# schema5.net
KiCad netlist of a schematic drawn in Altium Designer
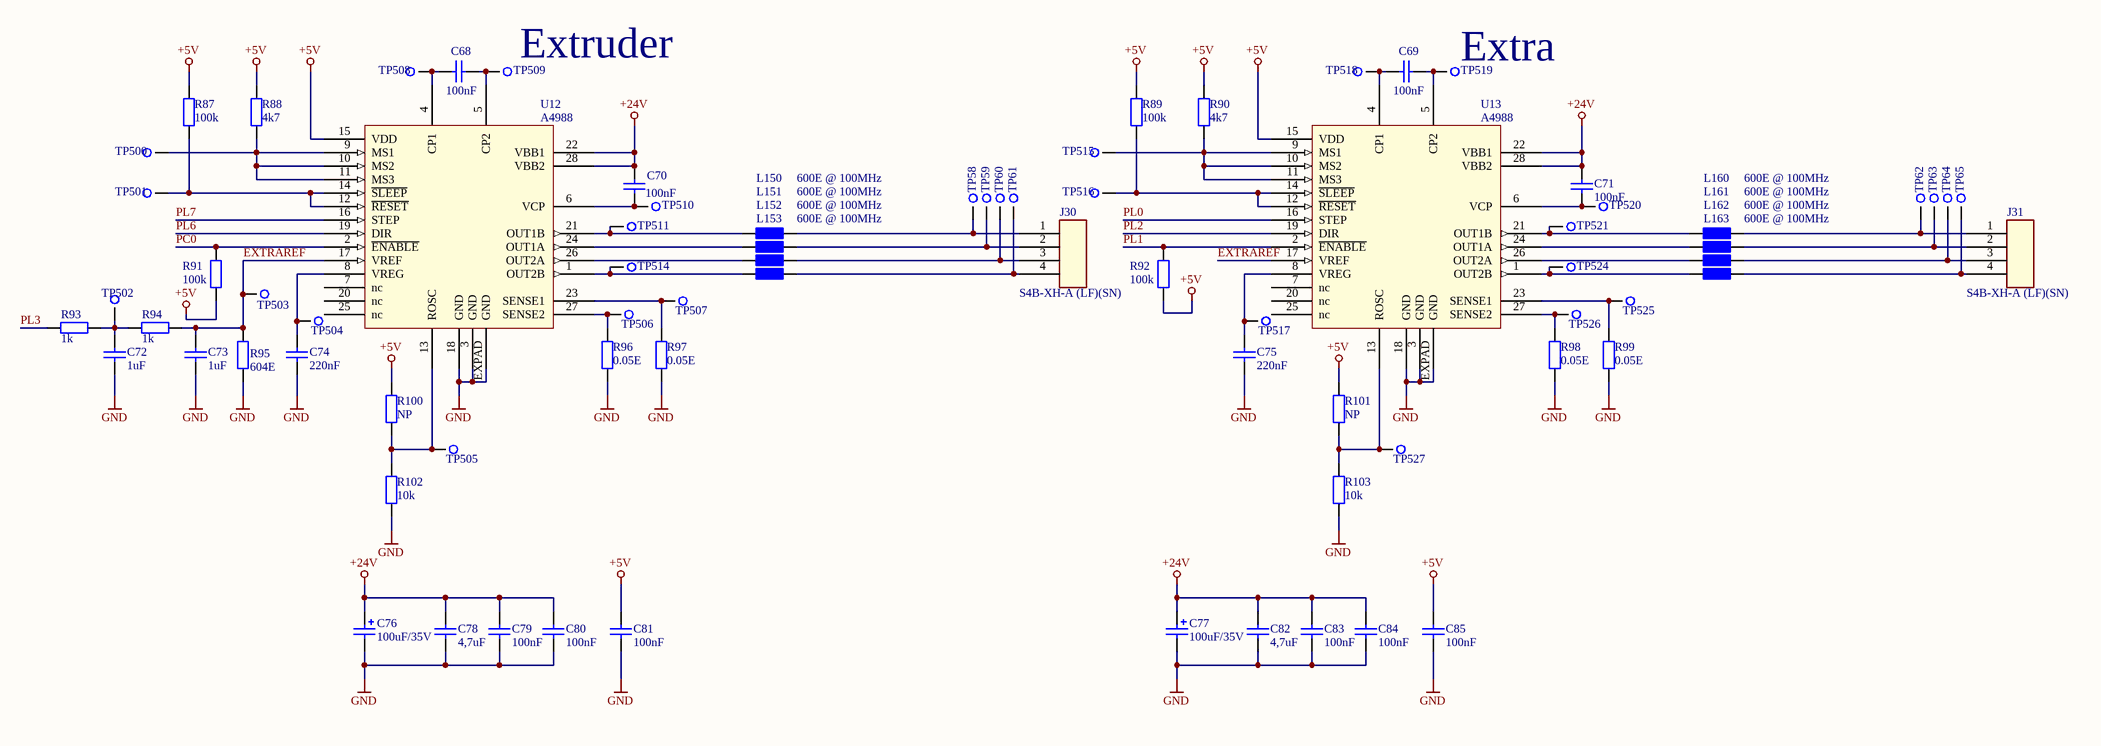
[diagram p0: schema5.SchDoc]

(export (version "E")
  (design (tool "Eeschema 10.0.6"))
  (components
    (comp (ref "C68")
      (value "100nF")
      (footprint "C0603")
      (description "RO X7R 100nF 10% 50V 0603")
      (libsource (lib "Database_Faber") (part "Capacitor"))
    )
    (comp (ref "C69")
      (value "100nF")
      (footprint "C0603")
      (description "RO X7R 100nF 10% 50V 0603")
      (libsource (lib "Database_Faber") (part "Capacitor"))
    )
    (comp (ref "C70")
      (value "100nF")
      (footprint "C0603")
      (description "RO X7R 100nF 10% 50V 0603")
      (libsource (lib "Database_Faber") (part "Capacitor"))
    )
    (comp (ref "C71")
      (value "100nF")
      (footprint "C0603")
      (description "RO X7R 100nF 10% 50V 0603")
      (libsource (lib "Database_Faber") (part "Capacitor"))
    )
    (comp (ref "C72")
      (value "1uF")
      (footprint "C0603")
      (description "RO X5R 1uF 10% 10V 0603")
      (libsource (lib "Database_Faber") (part "Capacitor"))
    )
    (comp (ref "C73")
      (value "1uF")
      (footprint "C0603")
      (description "RO X5R 1uF 10% 10V 0603")
      (libsource (lib "Database_Faber") (part "Capacitor"))
    )
    (comp (ref "C74")
      (value "220nF")
      (footprint "C0603")
      (description "RO X7R 220nF 10% 25V  0603")
      (libsource (lib "Database_Faber") (part "Capacitor"))
    )
    (comp (ref "C75")
      (value "220nF")
      (footprint "C0603")
      (description "RO X7R 220nF 10% 25V  0603")
      (libsource (lib "Database_Faber") (part "Capacitor"))
    )
    (comp (ref "C76")
      (value "100uF/35V")
      (footprint "ELCO Case D")
      (description "RO ELCO 100uF 20% 35V CASE-D EEEFP PAN")
      (libsource (lib "Database_Faber") (part "Capacitor Polarity"))
    )
    (comp (ref "C77")
      (value "100uF/35V")
      (footprint "ELCO Case D")
      (description "RO ELCO 100uF 20% 35V CASE-D EEEFP PAN")
      (libsource (lib "Database_Faber") (part "Capacitor Polarity"))
    )
    (comp (ref "C78")
      (value "4,7uF")
      (footprint "C1206")
      (description "RO X7R 4,7uF 10% 50V 1206")
      (libsource (lib "Database_Faber") (part "Capacitor"))
    )
    (comp (ref "C79")
      (value "100nF")
      (footprint "C0603")
      (description "RO X7R 100nF 10% 50V 0603")
      (libsource (lib "Database_Faber") (part "Capacitor"))
    )
    (comp (ref "C80")
      (value "100nF")
      (footprint "C0603")
      (description "RO X7R 100nF 10% 50V 0603")
      (libsource (lib "Database_Faber") (part "Capacitor"))
    )
    (comp (ref "C81")
      (value "100nF")
      (footprint "C0603")
      (description "RO X7R 100nF 10% 50V 0603")
      (libsource (lib "Database_Faber") (part "Capacitor"))
    )
    (comp (ref "C82")
      (value "4,7uF")
      (footprint "C1206")
      (description "RO X7R 4,7uF 10% 50V 1206")
      (libsource (lib "Database_Faber") (part "Capacitor"))
    )
    (comp (ref "C83")
      (value "100nF")
      (footprint "C0603")
      (description "RO X7R 100nF 10% 50V 0603")
      (libsource (lib "Database_Faber") (part "Capacitor"))
    )
    (comp (ref "C84")
      (value "100nF")
      (footprint "C0603")
      (description "RO X7R 100nF 10% 50V 0603")
      (libsource (lib "Database_Faber") (part "Capacitor"))
    )
    (comp (ref "C85")
      (value "100nF")
      (footprint "C0603")
      (description "RO X7R 100nF 10% 50V 0603")
      (libsource (lib "Database_Faber") (part "Capacitor"))
    )
    (comp (ref "J30")
      (value "S4B-XH-A (LF)(SN)")
      (footprint "S4B-XH-A (LF)(SN)")
      (description "RO CONN PR 4p HKS S4B-XH-A (LF)(SN) JST")
      (fields (field (name "MFG") "JST (JAPAN SOLDERLESS TERMINALS)"))
      (libsource (lib "Database_Faber") (part "HEADER 4"))
    )
    (comp (ref "J31")
      (value "S4B-XH-A (LF)(SN)")
      (footprint "S4B-XH-A (LF)(SN)")
      (description "RO CONN PR 4p HKS S4B-XH-A (LF)(SN) JST")
      (fields (field (name "MFG") "JST (JAPAN SOLDERLESS TERMINALS)"))
      (libsource (lib "Database_Faber") (part "HEADER 4"))
    )
    (comp (ref "L150")
      (value "600E @ 100MHz")
      (footprint "R1206")
      (description "FERRIET 742792118 1206 Wurth Elektronik")
      (fields (field (name "MFG") "Wurth Elektronics"))
      (libsource (lib "Ultimaker") (part "Ferriet Bead 600E"))
    )
    (comp (ref "L151")
      (value "600E @ 100MHz")
      (footprint "R1206")
      (description "FERRIET 742792118 1206 Wurth Elektronik")
      (fields (field (name "MFG") "Wurth Elektronics"))
      (libsource (lib "Ultimaker") (part "Ferriet Bead 600E"))
    )
    (comp (ref "L152")
      (value "600E @ 100MHz")
      (footprint "R1206")
      (description "FERRIET 742792118 1206 Wurth Elektronik")
      (fields (field (name "MFG") "Wurth Elektronics"))
      (libsource (lib "Ultimaker") (part "Ferriet Bead 600E"))
    )
    (comp (ref "L153")
      (value "600E @ 100MHz")
      (footprint "R1206")
      (description "FERRIET 742792118 1206 Wurth Elektronik")
      (fields (field (name "MFG") "Wurth Elektronics"))
      (libsource (lib "Ultimaker") (part "Ferriet Bead 600E"))
    )
    (comp (ref "L160")
      (value "600E @ 100MHz")
      (footprint "R1206")
      (description "FERRIET 742792118 1206 Wurth Elektronik")
      (fields (field (name "MFG") "Wurth Elektronics"))
      (libsource (lib "Ultimaker") (part "Ferriet Bead 600E"))
    )
    (comp (ref "L161")
      (value "600E @ 100MHz")
      (footprint "R1206")
      (description "FERRIET 742792118 1206 Wurth Elektronik")
      (fields (field (name "MFG") "Wurth Elektronics"))
      (libsource (lib "Ultimaker") (part "Ferriet Bead 600E"))
    )
    (comp (ref "L162")
      (value "600E @ 100MHz")
      (footprint "R1206")
      (description "FERRIET 742792118 1206 Wurth Elektronik")
      (fields (field (name "MFG") "Wurth Elektronics"))
      (libsource (lib "Ultimaker") (part "Ferriet Bead 600E"))
    )
    (comp (ref "L163")
      (value "600E @ 100MHz")
      (footprint "R1206")
      (description "FERRIET 742792118 1206 Wurth Elektronik")
      (fields (field (name "MFG") "Wurth Elektronics"))
      (libsource (lib "Ultimaker") (part "Ferriet Bead 600E"))
    )
    (comp (ref "R87")
      (value "100k")
      (footprint "R0603")
      (description "RO RES 100k0 1% 0,063W  0603")
      (libsource (lib "Database_Faber") (part "Resistor"))
    )
    (comp (ref "R88")
      (value "4k7")
      (footprint "R0603")
      (description "RO RES 4k70 1% 0,063W  0603")
      (libsource (lib "Database_Faber") (part "Resistor"))
    )
    (comp (ref "R89")
      (value "100k")
      (footprint "R0603")
      (description "RO RES 100k0 1% 0,063W  0603")
      (libsource (lib "Database_Faber") (part "Resistor"))
    )
    (comp (ref "R90")
      (value "4k7")
      (footprint "R0603")
      (description "RO RES 4k70 1% 0,063W  0603")
      (libsource (lib "Database_Faber") (part "Resistor"))
    )
    (comp (ref "R91")
      (value "100k")
      (footprint "R0603")
      (description "RO RES 100k0 1% 0,063W  0603")
      (libsource (lib "") (part "Resistor_2"))
    )
    (comp (ref "R92")
      (value "100k")
      (footprint "R0603")
      (description "RO RES 100k0 1% 0,063W  0603")
      (libsource (lib "") (part "Resistor_2"))
    )
    (comp (ref "R93")
      (value "1k")
      (footprint "R0603")
      (description "RO RES 1k0 1% 0,1W  0603")
      (libsource (lib "") (part "Resistor_1"))
    )
    (comp (ref "R94")
      (value "1k")
      (footprint "R0603")
      (description "RO RES 1k0 1% 0,1W  0603")
      (libsource (lib "") (part "Resistor_1"))
    )
    (comp (ref "R95")
      (value "604E")
      (footprint "R0603")
      (description "RO RES 604E 1% 0,063W 0603")
      (fields (field (name "MFG") "VISHAY DRALORIC"))
      (libsource (lib "Database_Faber") (part "Resistor"))
    )
    (comp (ref "R96")
      (value "0.05E")
      (footprint "R0805")
      (description "RO RES 0E05 1% 0,125W 0805")
      (fields (field (name "MFG") "BOURNS"))
      (libsource (lib "Database_Faber") (part "Resistor"))
    )
    (comp (ref "R97")
      (value "0.05E")
      (footprint "R0805")
      (description "RO RES 0E05 1% 0,125W 0805")
      (fields (field (name "MFG") "BOURNS"))
      (libsource (lib "Database_Faber") (part "Resistor"))
    )
    (comp (ref "R98")
      (value "0.05E")
      (footprint "R0805")
      (description "RO RES 0E05 1% 0,125W 0805")
      (fields (field (name "MFG") "BOURNS"))
      (libsource (lib "Database_Faber") (part "Resistor"))
    )
    (comp (ref "R99")
      (value "0.05E")
      (footprint "R0805")
      (description "RO RES 0E05 1% 0,125W 0805")
      (fields (field (name "MFG") "BOURNS"))
      (libsource (lib "Database_Faber") (part "Resistor"))
    )
    (comp (ref "R100") (value "NP") (footprint "R0603") (libsource (lib "Database_Faber") (part "Resistor")))
    (comp (ref "R101") (value "NP") (footprint "R0603") (libsource (lib "Database_Faber") (part "Resistor")))
    (comp (ref "R102")
      (value "10k")
      (footprint "R0603")
      (description "RO RES 10k0 1% 0,063W  0603")
      (libsource (lib "Database_Faber") (part "Resistor"))
    )
    (comp (ref "R103")
      (value "10k")
      (footprint "R0603")
      (description "RO RES 10k0 1% 0,063W  0603")
      (libsource (lib "Database_Faber") (part "Resistor"))
    )
    (comp (ref "TP58")
      (value "Testpoint")
      (footprint "Testpoint")
      (libsource (lib "Database_Faber") (part "Testpoint"))
    )
    (comp (ref "TP59")
      (value "Testpoint")
      (footprint "Testpoint")
      (libsource (lib "Database_Faber") (part "Testpoint"))
    )
    (comp (ref "TP60")
      (value "Testpoint")
      (footprint "Testpoint")
      (libsource (lib "Database_Faber") (part "Testpoint"))
    )
    (comp (ref "TP61")
      (value "Testpoint")
      (footprint "Testpoint")
      (libsource (lib "Database_Faber") (part "Testpoint"))
    )
    (comp (ref "TP62")
      (value "Testpoint")
      (footprint "Testpoint")
      (libsource (lib "Database_Faber") (part "Testpoint"))
    )
    (comp (ref "TP63")
      (value "Testpoint")
      (footprint "Testpoint")
      (libsource (lib "Database_Faber") (part "Testpoint"))
    )
    (comp (ref "TP64")
      (value "Testpoint")
      (footprint "Testpoint")
      (libsource (lib "Database_Faber") (part "Testpoint"))
    )
    (comp (ref "TP65")
      (value "Testpoint")
      (footprint "Testpoint")
      (libsource (lib "Database_Faber") (part "Testpoint"))
    )
    (comp (ref "TP500")
      (value "Testpoint")
      (footprint "TESTPOINT")
      (libsource (lib "Ultimaker") (part "Testpoint 1mm"))
    )
    (comp (ref "TP501")
      (value "Testpoint")
      (footprint "TESTPOINT")
      (libsource (lib "Ultimaker") (part "Testpoint 1mm"))
    )
    (comp (ref "TP502")
      (value "Testpoint 1mm")
      (footprint "Testpoint 1mm")
      (libsource (lib "Ultimaker") (part "Testpoint 1mm"))
    )
    (comp (ref "TP503")
      (value "Testpoint 1mm")
      (footprint "Testpoint 1mm")
      (libsource (lib "Ultimaker") (part "Testpoint 1mm"))
    )
    (comp (ref "TP504")
      (value "Testpoint 1mm")
      (footprint "Testpoint 1mm")
      (libsource (lib "Ultimaker") (part "Testpoint 1mm"))
    )
    (comp (ref "TP505")
      (value "Testpoint 1mm")
      (footprint "Testpoint 1mm")
      (libsource (lib "Ultimaker") (part "Testpoint 1mm"))
    )
    (comp (ref "TP506")
      (value "Testpoint 1mm")
      (footprint "Testpoint 1mm")
      (libsource (lib "Ultimaker") (part "Testpoint 1mm"))
    )
    (comp (ref "TP507")
      (value "Testpoint 1mm")
      (footprint "Testpoint 1mm")
      (libsource (lib "Ultimaker") (part "Testpoint 1mm"))
    )
    (comp (ref "TP508")
      (value "Testpoint 1mm")
      (footprint "Testpoint 1mm")
      (libsource (lib "Ultimaker") (part "Testpoint 1mm"))
    )
    (comp (ref "TP509")
      (value "Testpoint 1mm")
      (footprint "Testpoint 1mm")
      (libsource (lib "Ultimaker") (part "Testpoint 1mm"))
    )
    (comp (ref "TP510")
      (value "Testpoint 1mm")
      (footprint "Testpoint 1mm")
      (libsource (lib "Ultimaker") (part "Testpoint 1mm"))
    )
    (comp (ref "TP511")
      (value "Testpoint 1mm")
      (footprint "Testpoint 1mm")
      (libsource (lib "Ultimaker") (part "Testpoint 1mm"))
    )
    (comp (ref "TP514")
      (value "Testpoint 1mm")
      (footprint "Testpoint 1mm")
      (libsource (lib "Ultimaker") (part "Testpoint 1mm"))
    )
    (comp (ref "TP515")
      (value "Testpoint")
      (footprint "TESTPOINT")
      (libsource (lib "Ultimaker") (part "Testpoint 1mm"))
    )
    (comp (ref "TP516")
      (value "Testpoint")
      (footprint "TESTPOINT")
      (libsource (lib "Ultimaker") (part "Testpoint 1mm"))
    )
    (comp (ref "TP517")
      (value "Testpoint 1mm")
      (footprint "Testpoint 1mm")
      (libsource (lib "Ultimaker") (part "Testpoint 1mm"))
    )
    (comp (ref "TP518")
      (value "Testpoint 1mm")
      (footprint "Testpoint 1mm")
      (libsource (lib "Ultimaker") (part "Testpoint 1mm"))
    )
    (comp (ref "TP519")
      (value "Testpoint 1mm")
      (footprint "Testpoint 1mm")
      (libsource (lib "Ultimaker") (part "Testpoint 1mm"))
    )
    (comp (ref "TP520")
      (value "Testpoint 1mm")
      (footprint "Testpoint 1mm")
      (libsource (lib "Ultimaker") (part "Testpoint 1mm"))
    )
    (comp (ref "TP521")
      (value "Testpoint 1mm")
      (footprint "Testpoint 1mm")
      (libsource (lib "Ultimaker") (part "Testpoint 1mm"))
    )
    (comp (ref "TP524")
      (value "Testpoint 1mm")
      (footprint "Testpoint 1mm")
      (libsource (lib "Ultimaker") (part "Testpoint 1mm"))
    )
    (comp (ref "TP525")
      (value "Testpoint 1mm")
      (footprint "Testpoint 1mm")
      (libsource (lib "Ultimaker") (part "Testpoint 1mm"))
    )
    (comp (ref "TP526")
      (value "Testpoint 1mm")
      (footprint "Testpoint 1mm")
      (libsource (lib "Ultimaker") (part "Testpoint 1mm"))
    )
    (comp (ref "TP527")
      (value "Testpoint 1mm")
      (footprint "Testpoint 1mm")
      (libsource (lib "Ultimaker") (part "Testpoint 1mm"))
    )
    (comp (ref "U12")
      (value "A4988")
      (footprint "QFN50P500X500X100-28-EX")
      (description "RO IC A4988 QFN-28 ALLEGRO")
      (fields (field (name "MFG") "Allegro"))
      (libsource (lib "Database_Faber") (part "A4988"))
    )
    (comp (ref "U13")
      (value "A4988")
      (footprint "QFN50P500X500X100-28-EX")
      (description "RO IC A4988 QFN-28 ALLEGRO")
      (fields (field (name "MFG") "Allegro"))
      (libsource (lib "Database_Faber") (part "A4988"))
    )
  )
  (nets
    (net (code "1") (name "+5V") (class "Default")
      (node (ref "C81") (pin "2") (pinfunction "2_2") (pintype "passive"))
      (node (ref "C85") (pin "2") (pinfunction "2_2") (pintype "passive"))
      (node (ref "R100") (pin "2") (pinfunction "2_2") (pintype "passive"))
      (node (ref "R101") (pin "2") (pinfunction "2_2") (pintype "passive"))
      (node (ref "R87") (pin "2") (pinfunction "2_2") (pintype "passive"))
      (node (ref "R88") (pin "2") (pinfunction "2_2") (pintype "passive"))
      (node (ref "R89") (pin "2") (pinfunction "2_2") (pintype "passive"))
      (node (ref "R90") (pin "2") (pinfunction "2_2") (pintype "passive"))
      (node (ref "R91") (pin "2") (pinfunction "2_2") (pintype "passive"))
      (node (ref "R92") (pin "2") (pinfunction "2_2") (pintype "passive"))
      (node (ref "U12") (pin "15") (pinfunction "VDD_15") (pintype "power_in"))
      (node (ref "U13") (pin "15") (pinfunction "VDD_15") (pintype "power_in"))
    )
    (net (code "2") (name "+24V") (class "Default")
      (node (ref "C70") (pin "2") (pinfunction "2_2") (pintype "passive"))
      (node (ref "C71") (pin "2") (pinfunction "2_2") (pintype "passive"))
      (node (ref "C76") (pin "1") (pinfunction "1_1") (pintype "passive"))
      (node (ref "C77") (pin "1") (pinfunction "1_1") (pintype "passive"))
      (node (ref "C78") (pin "2") (pinfunction "2_2") (pintype "passive"))
      (node (ref "C79") (pin "2") (pinfunction "2_2") (pintype "passive"))
      (node (ref "C80") (pin "2") (pinfunction "2_2") (pintype "passive"))
      (node (ref "C82") (pin "2") (pinfunction "2_2") (pintype "passive"))
      (node (ref "C83") (pin "2") (pinfunction "2_2") (pintype "passive"))
      (node (ref "C84") (pin "2") (pinfunction "2_2") (pintype "passive"))
      (node (ref "U12") (pin "22") (pinfunction "VBB1_22") (pintype "power_in"))
      (node (ref "U12") (pin "28") (pinfunction "VBB2_28") (pintype "power_in"))
      (node (ref "U13") (pin "22") (pinfunction "VBB1_22") (pintype "power_in"))
      (node (ref "U13") (pin "28") (pinfunction "VBB2_28") (pintype "power_in"))
    )
    (net (code "3") (name "/EXTRAREF") (class "Default")
      (node (ref "C73") (pin "2") (pinfunction "2_2") (pintype "passive"))
      (node (ref "R94") (pin "2") (pinfunction "2_2") (pintype "passive"))
      (node (ref "R95") (pin "2") (pinfunction "2_2") (pintype "passive"))
      (node (ref "TP503") (pin "1") (pinfunction "1_1") (pintype "passive"))
      (node (ref "U12") (pin "17") (pinfunction "VREF_17") (pintype "input"))
      (node (ref "U13") (pin "17") (pinfunction "VREF_17") (pintype "input"))
    )
    (net (code "4") (name "/PC0") (class "Default")
      (node (ref "R91") (pin "1") (pinfunction "1_1") (pintype "passive"))
      (node (ref "U12") (pin "2") (pinfunction "~{ENABLE}_2") (pintype "input"))
    )
    (net (code "5") (name "/PL0") (class "Default")
      (node (ref "U13") (pin "16") (pinfunction "STEP_16") (pintype "input"))
    )
    (net (code "6") (name "/PL1") (class "Default")
      (node (ref "R92") (pin "1") (pinfunction "1_1") (pintype "passive"))
      (node (ref "U13") (pin "2") (pinfunction "~{ENABLE}_2") (pintype "input"))
    )
    (net (code "7") (name "/PL2") (class "Default")
      (node (ref "U13") (pin "19") (pinfunction "DIR_19") (pintype "input"))
    )
    (net (code "8") (name "/PL3") (class "Default")
      (node (ref "R93") (pin "1") (pinfunction "1_1") (pintype "passive"))
    )
    (net (code "9") (name "/PL6") (class "Default")
      (node (ref "U12") (pin "19") (pinfunction "DIR_19") (pintype "input"))
    )
    (net (code "10") (name "/PL7") (class "Default")
      (node (ref "U12") (pin "16") (pinfunction "STEP_16") (pintype "input"))
    )
    (net (code "11") (name "GND") (class "Default")
      (node (ref "C72") (pin "1") (pinfunction "1_1") (pintype "passive"))
      (node (ref "C73") (pin "1") (pinfunction "1_1") (pintype "passive"))
      (node (ref "C74") (pin "1") (pinfunction "1_1") (pintype "passive"))
      (node (ref "C75") (pin "1") (pinfunction "1_1") (pintype "passive"))
      (node (ref "C76") (pin "2") (pinfunction "2_2") (pintype "passive"))
      (node (ref "C77") (pin "2") (pinfunction "2_2") (pintype "passive"))
      (node (ref "C78") (pin "1") (pinfunction "1_1") (pintype "passive"))
      (node (ref "C79") (pin "1") (pinfunction "1_1") (pintype "passive"))
      (node (ref "C80") (pin "1") (pinfunction "1_1") (pintype "passive"))
      (node (ref "C81") (pin "1") (pinfunction "1_1") (pintype "passive"))
      (node (ref "C82") (pin "1") (pinfunction "1_1") (pintype "passive"))
      (node (ref "C83") (pin "1") (pinfunction "1_1") (pintype "passive"))
      (node (ref "C84") (pin "1") (pinfunction "1_1") (pintype "passive"))
      (node (ref "C85") (pin "1") (pinfunction "1_1") (pintype "passive"))
      (node (ref "R102") (pin "1") (pinfunction "1_1") (pintype "passive"))
      (node (ref "R103") (pin "1") (pinfunction "1_1") (pintype "passive"))
      (node (ref "R95") (pin "1") (pinfunction "1_1") (pintype "passive"))
      (node (ref "R96") (pin "1") (pinfunction "1_1") (pintype "passive"))
      (node (ref "R97") (pin "1") (pinfunction "1_1") (pintype "passive"))
      (node (ref "R98") (pin "1") (pinfunction "1_1") (pintype "passive"))
      (node (ref "R99") (pin "1") (pinfunction "1_1") (pintype "passive"))
      (node (ref "U12") (pin "18") (pinfunction "GND_18") (pintype "passive"))
      (node (ref "U12") (pin "3") (pinfunction "GND_3") (pintype "power_in"))
      (node (ref "U12") (pin "EXPAD") (pinfunction "GND_EXPAD") (pintype "power_in"))
      (node (ref "U13") (pin "18") (pinfunction "GND_18") (pintype "passive"))
      (node (ref "U13") (pin "3") (pinfunction "GND_3") (pintype "power_in"))
      (node (ref "U13") (pin "EXPAD") (pinfunction "GND_EXPAD") (pintype "power_in"))
    )
    (net (code "12") (name "Net-(C72-Pad2)") (class "Default")
      (node (ref "C72") (pin "2") (pinfunction "2_2") (pintype "passive"))
      (node (ref "R93") (pin "2") (pinfunction "2_2") (pintype "passive"))
      (node (ref "R94") (pin "1") (pinfunction "1_1") (pintype "passive"))
      (node (ref "TP502") (pin "1") (pinfunction "1_1") (pintype "passive"))
    )
    (net (code "13") (name "Net-(J30-Pad1)") (class "Default")
      (node (ref "J30") (pin "1") (pinfunction "1_1") (pintype "passive"))
      (node (ref "L150") (pin "2") (pinfunction "2_2") (pintype "passive"))
      (node (ref "TP58") (pin "1") (pinfunction "1_1") (pintype "passive"))
    )
    (net (code "14") (name "Net-(J30-Pad2)") (class "Default")
      (node (ref "J30") (pin "2") (pinfunction "2_2") (pintype "passive"))
      (node (ref "L151") (pin "2") (pinfunction "2_2") (pintype "passive"))
      (node (ref "TP59") (pin "1") (pinfunction "1_1") (pintype "passive"))
    )
    (net (code "15") (name "Net-(J30-Pad3)") (class "Default")
      (node (ref "J30") (pin "3") (pinfunction "3_3") (pintype "passive"))
      (node (ref "L152") (pin "2") (pinfunction "2_2") (pintype "passive"))
      (node (ref "TP60") (pin "1") (pinfunction "1_1") (pintype "passive"))
    )
    (net (code "16") (name "Net-(J30-Pad4)") (class "Default")
      (node (ref "J30") (pin "4") (pinfunction "4_4") (pintype "passive"))
      (node (ref "L153") (pin "2") (pinfunction "2_2") (pintype "passive"))
      (node (ref "TP61") (pin "1") (pinfunction "1_1") (pintype "passive"))
    )
    (net (code "17") (name "Net-(J31-Pad1)") (class "Default")
      (node (ref "J31") (pin "1") (pinfunction "1_1") (pintype "passive"))
      (node (ref "L160") (pin "2") (pinfunction "2_2") (pintype "passive"))
      (node (ref "TP62") (pin "1") (pinfunction "1_1") (pintype "passive"))
    )
    (net (code "18") (name "Net-(J31-Pad2)") (class "Default")
      (node (ref "J31") (pin "2") (pinfunction "2_2") (pintype "passive"))
      (node (ref "L161") (pin "2") (pinfunction "2_2") (pintype "passive"))
      (node (ref "TP63") (pin "1") (pinfunction "1_1") (pintype "passive"))
    )
    (net (code "19") (name "Net-(J31-Pad3)") (class "Default")
      (node (ref "J31") (pin "3") (pinfunction "3_3") (pintype "passive"))
      (node (ref "L162") (pin "2") (pinfunction "2_2") (pintype "passive"))
      (node (ref "TP64") (pin "1") (pinfunction "1_1") (pintype "passive"))
    )
    (net (code "20") (name "Net-(J31-Pad4)") (class "Default")
      (node (ref "J31") (pin "4") (pinfunction "4_4") (pintype "passive"))
      (node (ref "L163") (pin "2") (pinfunction "2_2") (pintype "passive"))
      (node (ref "TP65") (pin "1") (pinfunction "1_1") (pintype "passive"))
    )
    (net (code "21") (name "Net-(U12-CP1)") (class "Default")
      (node (ref "C68") (pin "1") (pinfunction "1_1") (pintype "passive"))
      (node (ref "TP508") (pin "1") (pinfunction "1_1") (pintype "passive"))
      (node (ref "U12") (pin "4") (pinfunction "CP1_4") (pintype "passive"))
    )
    (net (code "22") (name "Net-(U12-CP2)") (class "Default")
      (node (ref "C68") (pin "2") (pinfunction "2_2") (pintype "passive"))
      (node (ref "TP509") (pin "1") (pinfunction "1_1") (pintype "passive"))
      (node (ref "U12") (pin "5") (pinfunction "CP2_5") (pintype "passive"))
    )
    (net (code "23") (name "Net-(U12-MS1)") (class "Default")
      (node (ref "R88") (pin "1") (pinfunction "1_1") (pintype "passive"))
      (node (ref "TP500") (pin "1") (pinfunction "1_1") (pintype "passive"))
      (node (ref "U12") (pin "10") (pinfunction "MS2_10") (pintype "input"))
      (node (ref "U12") (pin "11") (pinfunction "MS3_11") (pintype "input"))
      (node (ref "U12") (pin "9") (pinfunction "MS1_9") (pintype "input"))
    )
    (net (code "24") (name "Net-(U12-OUT1A)") (class "Default")
      (node (ref "L151") (pin "1") (pinfunction "1_1") (pintype "passive"))
      (node (ref "U12") (pin "24") (pinfunction "OUT1A_24") (pintype "output"))
    )
    (net (code "25") (name "Net-(U12-OUT1B)") (class "Default")
      (node (ref "L150") (pin "1") (pinfunction "1_1") (pintype "passive"))
      (node (ref "TP511") (pin "1") (pinfunction "1_1") (pintype "passive"))
      (node (ref "U12") (pin "21") (pinfunction "OUT1B_21") (pintype "output"))
    )
    (net (code "26") (name "Net-(U12-OUT2A)") (class "Default")
      (node (ref "L152") (pin "1") (pinfunction "1_1") (pintype "passive"))
      (node (ref "U12") (pin "26") (pinfunction "OUT2A_26") (pintype "output"))
    )
    (net (code "27") (name "Net-(U12-OUT2B)") (class "Default")
      (node (ref "L153") (pin "1") (pinfunction "1_1") (pintype "passive"))
      (node (ref "TP514") (pin "1") (pinfunction "1_1") (pintype "passive"))
      (node (ref "U12") (pin "1") (pinfunction "OUT2B_1") (pintype "output"))
    )
    (net (code "28") (name "Net-(U12-ROSC)") (class "Default")
      (node (ref "R100") (pin "1") (pinfunction "1_1") (pintype "passive"))
      (node (ref "R102") (pin "2") (pinfunction "2_2") (pintype "passive"))
      (node (ref "TP505") (pin "1") (pinfunction "1_1") (pintype "passive"))
      (node (ref "U12") (pin "13") (pinfunction "ROSC_13") (pintype "passive"))
    )
    (net (code "29") (name "Net-(U12-SENSE1)") (class "Default")
      (node (ref "R97") (pin "2") (pinfunction "2_2") (pintype "passive"))
      (node (ref "TP507") (pin "1") (pinfunction "1_1") (pintype "passive"))
      (node (ref "U12") (pin "23") (pinfunction "SENSE1_23") (pintype "passive"))
    )
    (net (code "30") (name "Net-(U12-SENSE2)") (class "Default")
      (node (ref "R96") (pin "2") (pinfunction "2_2") (pintype "passive"))
      (node (ref "TP506") (pin "1") (pinfunction "1_1") (pintype "passive"))
      (node (ref "U12") (pin "27") (pinfunction "SENSE2_27") (pintype "passive"))
    )
    (net (code "31") (name "Net-(U12-VCP)") (class "Default")
      (node (ref "C70") (pin "1") (pinfunction "1_1") (pintype "passive"))
      (node (ref "TP510") (pin "1") (pinfunction "1_1") (pintype "passive"))
      (node (ref "U12") (pin "6") (pinfunction "VCP_6") (pintype "passive"))
    )
    (net (code "32") (name "Net-(U12-VREG)") (class "Default")
      (node (ref "C74") (pin "2") (pinfunction "2_2") (pintype "passive"))
      (node (ref "TP504") (pin "1") (pinfunction "1_1") (pintype "passive"))
      (node (ref "U12") (pin "8") (pinfunction "VREG_8") (pintype "power_in"))
    )
    (net (code "33") (name "Net-(U12-~{RESET})") (class "Default")
      (node (ref "R87") (pin "1") (pinfunction "1_1") (pintype "passive"))
      (node (ref "TP501") (pin "1") (pinfunction "1_1") (pintype "passive"))
      (node (ref "U12") (pin "12") (pinfunction "~{RESET}_12") (pintype "input"))
      (node (ref "U12") (pin "14") (pinfunction "~{SLEEP}_14") (pintype "input"))
    )
    (net (code "34") (name "Net-(U13-CP1)") (class "Default")
      (node (ref "C69") (pin "1") (pinfunction "1_1") (pintype "passive"))
      (node (ref "TP518") (pin "1") (pinfunction "1_1") (pintype "passive"))
      (node (ref "U13") (pin "4") (pinfunction "CP1_4") (pintype "passive"))
    )
    (net (code "35") (name "Net-(U13-CP2)") (class "Default")
      (node (ref "C69") (pin "2") (pinfunction "2_2") (pintype "passive"))
      (node (ref "TP519") (pin "1") (pinfunction "1_1") (pintype "passive"))
      (node (ref "U13") (pin "5") (pinfunction "CP2_5") (pintype "passive"))
    )
    (net (code "36") (name "Net-(U13-MS1)") (class "Default")
      (node (ref "R90") (pin "1") (pinfunction "1_1") (pintype "passive"))
      (node (ref "TP515") (pin "1") (pinfunction "1_1") (pintype "passive"))
      (node (ref "U13") (pin "10") (pinfunction "MS2_10") (pintype "input"))
      (node (ref "U13") (pin "11") (pinfunction "MS3_11") (pintype "input"))
      (node (ref "U13") (pin "9") (pinfunction "MS1_9") (pintype "input"))
    )
    (net (code "37") (name "Net-(U13-OUT1A)") (class "Default")
      (node (ref "L161") (pin "1") (pinfunction "1_1") (pintype "passive"))
      (node (ref "U13") (pin "24") (pinfunction "OUT1A_24") (pintype "output"))
    )
    (net (code "38") (name "Net-(U13-OUT1B)") (class "Default")
      (node (ref "L160") (pin "1") (pinfunction "1_1") (pintype "passive"))
      (node (ref "TP521") (pin "1") (pinfunction "1_1") (pintype "passive"))
      (node (ref "U13") (pin "21") (pinfunction "OUT1B_21") (pintype "output"))
    )
    (net (code "39") (name "Net-(U13-OUT2A)") (class "Default")
      (node (ref "L162") (pin "1") (pinfunction "1_1") (pintype "passive"))
      (node (ref "U13") (pin "26") (pinfunction "OUT2A_26") (pintype "output"))
    )
    (net (code "40") (name "Net-(U13-OUT2B)") (class "Default")
      (node (ref "L163") (pin "1") (pinfunction "1_1") (pintype "passive"))
      (node (ref "TP524") (pin "1") (pinfunction "1_1") (pintype "passive"))
      (node (ref "U13") (pin "1") (pinfunction "OUT2B_1") (pintype "output"))
    )
    (net (code "41") (name "Net-(U13-ROSC)") (class "Default")
      (node (ref "R101") (pin "1") (pinfunction "1_1") (pintype "passive"))
      (node (ref "R103") (pin "2") (pinfunction "2_2") (pintype "passive"))
      (node (ref "TP527") (pin "1") (pinfunction "1_1") (pintype "passive"))
      (node (ref "U13") (pin "13") (pinfunction "ROSC_13") (pintype "passive"))
    )
    (net (code "42") (name "Net-(U13-SENSE1)") (class "Default")
      (node (ref "R99") (pin "2") (pinfunction "2_2") (pintype "passive"))
      (node (ref "TP525") (pin "1") (pinfunction "1_1") (pintype "passive"))
      (node (ref "U13") (pin "23") (pinfunction "SENSE1_23") (pintype "passive"))
    )
    (net (code "43") (name "Net-(U13-SENSE2)") (class "Default")
      (node (ref "R98") (pin "2") (pinfunction "2_2") (pintype "passive"))
      (node (ref "TP526") (pin "1") (pinfunction "1_1") (pintype "passive"))
      (node (ref "U13") (pin "27") (pinfunction "SENSE2_27") (pintype "passive"))
    )
    (net (code "44") (name "Net-(U13-VCP)") (class "Default")
      (node (ref "C71") (pin "1") (pinfunction "1_1") (pintype "passive"))
      (node (ref "TP520") (pin "1") (pinfunction "1_1") (pintype "passive"))
      (node (ref "U13") (pin "6") (pinfunction "VCP_6") (pintype "passive"))
    )
    (net (code "45") (name "Net-(U13-VREG)") (class "Default")
      (node (ref "C75") (pin "2") (pinfunction "2_2") (pintype "passive"))
      (node (ref "TP517") (pin "1") (pinfunction "1_1") (pintype "passive"))
      (node (ref "U13") (pin "8") (pinfunction "VREG_8") (pintype "power_in"))
    )
    (net (code "46") (name "Net-(U13-~{RESET})") (class "Default")
      (node (ref "R89") (pin "1") (pinfunction "1_1") (pintype "passive"))
      (node (ref "TP516") (pin "1") (pinfunction "1_1") (pintype "passive"))
      (node (ref "U13") (pin "12") (pinfunction "~{RESET}_12") (pintype "input"))
      (node (ref "U13") (pin "14") (pinfunction "~{SLEEP}_14") (pintype "input"))
    )
    (net (code "47") (name "unconnected-(U12-nc-Pad7)") (class "Default")
      (node (ref "U12") (pin "7") (pinfunction "nc_7") (pintype "passive"))
    )
    (net (code "48") (name "unconnected-(U12-nc-Pad20)") (class "Default")
      (node (ref "U12") (pin "20") (pinfunction "nc_20") (pintype "passive"))
    )
    (net (code "49") (name "unconnected-(U12-nc-Pad25)") (class "Default")
      (node (ref "U12") (pin "25") (pinfunction "nc_25") (pintype "passive"))
    )
    (net (code "50") (name "unconnected-(U13-nc-Pad7)") (class "Default")
      (node (ref "U13") (pin "7") (pinfunction "nc_7") (pintype "passive"))
    )
    (net (code "51") (name "unconnected-(U13-nc-Pad20)") (class "Default")
      (node (ref "U13") (pin "20") (pinfunction "nc_20") (pintype "passive"))
    )
    (net (code "52") (name "unconnected-(U13-nc-Pad25)") (class "Default")
      (node (ref "U13") (pin "25") (pinfunction "nc_25") (pintype "passive"))
    )
  )
)
